# Main.net
KiCad netlist of a schematic drawn in Altium Designer
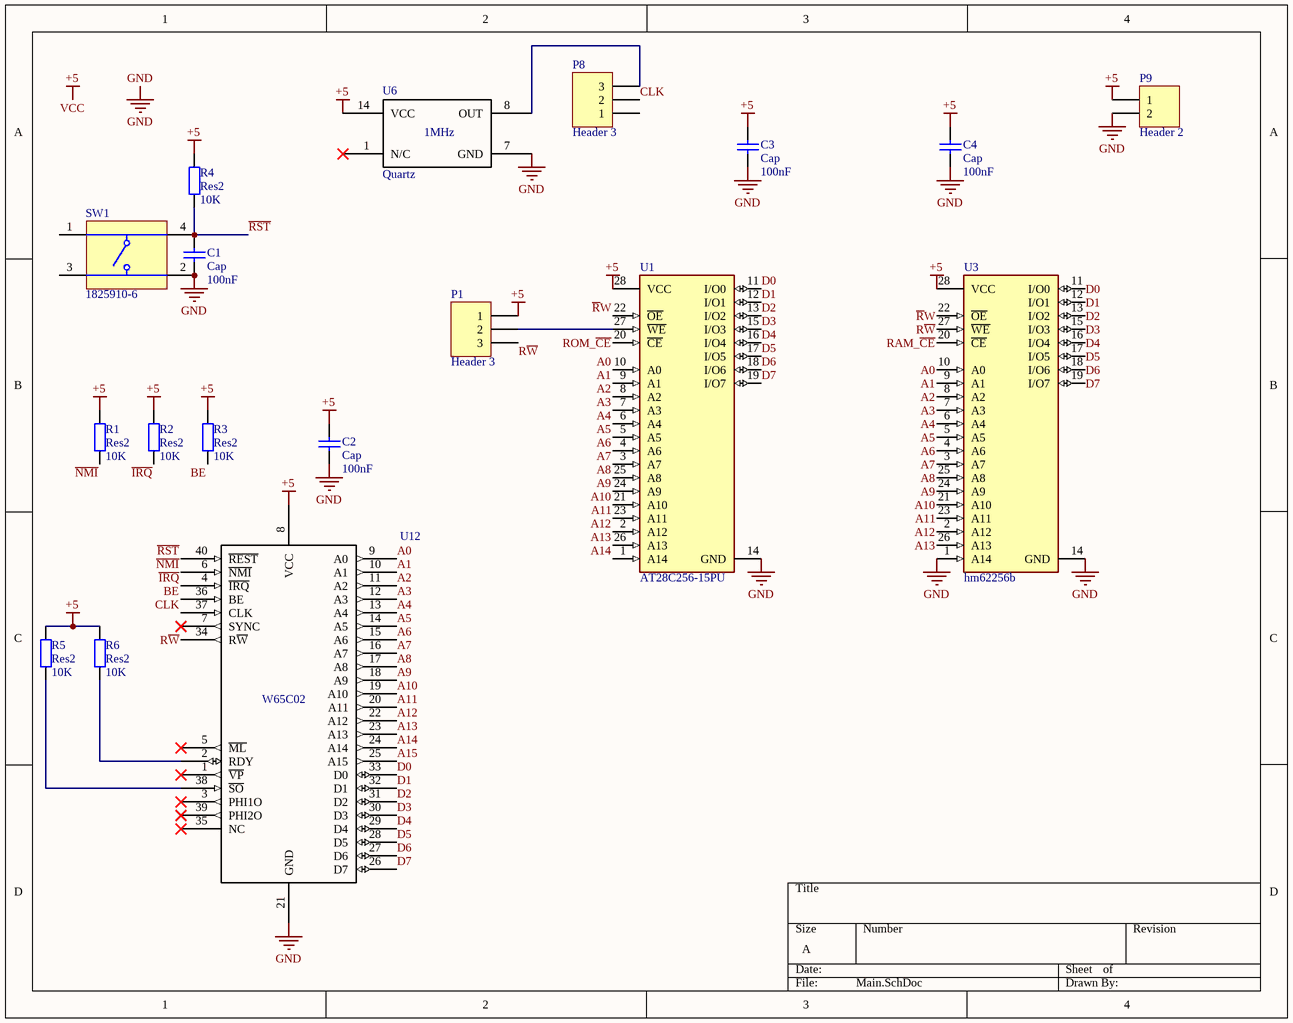
[diagram p0: Main.SchDoc]

(export (version "E")
  (design (tool "Eeschema 10.0.6"))
  (components
    (comp (ref "C1")
      (value "Cap")
      (footprint "Ceramic Capacitor")
      (description "Capacitor")
      (fields (field (name "ALTIUM_VALUE") "100nF") (field (name "PUBLISHER") "Altium Limited"))
      (libsource (lib "Miscellaneous Devices") (part "Cap"))
    )
    (comp (ref "C2")
      (value "Cap")
      (footprint "Ceramic Capacitor")
      (description "Capacitor")
      (fields (field (name "ALTIUM_VALUE") "100nF") (field (name "PUBLISHER") "Altium Limited"))
      (libsource (lib "Miscellaneous Devices") (part "Cap"))
    )
    (comp (ref "C3")
      (value "Cap")
      (footprint "Ceramic Capacitor")
      (description "Capacitor")
      (fields (field (name "ALTIUM_VALUE") "100nF") (field (name "PUBLISHER") "Altium Limited"))
      (libsource (lib "Miscellaneous Devices") (part "Cap"))
    )
    (comp (ref "C4")
      (value "Cap")
      (footprint "Ceramic Capacitor")
      (description "Capacitor")
      (fields (field (name "ALTIUM_VALUE") "100nF") (field (name "PUBLISHER") "Altium Limited"))
      (libsource (lib "Miscellaneous Devices") (part "Cap"))
    )
    (comp (ref "P1")
      (value "Header 3")
      (footprint "HDR1X3")
      (description "Header, 3-Pin")
      (fields (field (name "PUBLISHER") "Altium Limited"))
      (libsource (lib "") (part "Header 3_1"))
    )
    (comp (ref "P8")
      (value "Header 3")
      (footprint "HDR1X3")
      (description "Header, 3-Pin")
      (fields (field (name "PUBLISHER") "Altium Limited"))
      (libsource (lib "Miscellaneous Connectors") (part "Header 3"))
    )
    (comp (ref "P9")
      (value "Header 2")
      (footprint "HDR1X2")
      (description "Header, 2-Pin")
      (fields (field (name "PUBLISHER") "Altium Limited"))
      (libsource (lib "Miscellaneous Connectors") (part "Header 2"))
    )
    (comp (ref "R1")
      (value "Res2")
      (footprint "AXIAL-0.4")
      (description "Resistor")
      (fields (field (name "ALTIUM_VALUE") "10K") (field (name "PUBLISHER") "Altium Limited"))
      (libsource (lib "Miscellaneous Devices") (part "Res2"))
    )
    (comp (ref "R2")
      (value "Res2")
      (footprint "AXIAL-0.4")
      (description "Resistor")
      (fields (field (name "ALTIUM_VALUE") "10K") (field (name "PUBLISHER") "Altium Limited"))
      (libsource (lib "Miscellaneous Devices") (part "Res2"))
    )
    (comp (ref "R3")
      (value "Res2")
      (footprint "AXIAL-0.4")
      (description "Resistor")
      (fields (field (name "ALTIUM_VALUE") "10K") (field (name "PUBLISHER") "Altium Limited"))
      (libsource (lib "Miscellaneous Devices") (part "Res2"))
    )
    (comp (ref "R4")
      (value "Res2")
      (footprint "AXIAL-0.4")
      (description "Resistor")
      (fields (field (name "ALTIUM_VALUE") "10K") (field (name "PUBLISHER") "Altium Limited"))
      (libsource (lib "Miscellaneous Devices") (part "Res2"))
    )
    (comp (ref "R5")
      (value "Res2")
      (footprint "AXIAL-0.4")
      (description "Resistor")
      (fields (field (name "ALTIUM_VALUE") "10K") (field (name "PUBLISHER") "Altium Limited"))
      (libsource (lib "Miscellaneous Devices") (part "Res2"))
    )
    (comp (ref "R6")
      (value "Res2")
      (footprint "AXIAL-0.4")
      (description "Resistor")
      (fields (field (name "ALTIUM_VALUE") "10K") (field (name "PUBLISHER") "Altium Limited"))
      (libsource (lib "Miscellaneous Devices") (part "Res2"))
    )
    (comp (ref "SW1")
      (value "1825910-6")
      (footprint "TECO-1825910-6_V")
      (description "Tact Switch, SPST-NO, 0.05 A, -35 to 85 degC, 4-Pin THD, RoHS, Bulk")
      (fields (field (name "MANUFACTURER") "TE Connectivity"))
      (libsource (lib "Altium Content Vault") (part "SW-SPST-4_A"))
    )
    (comp (ref "U1")
      (value "AT28C256-15PU")
      (footprint "FP-28P6-MFG")
      (description "IC EEPROM 256K PARALLEL 28DIP")
      (fields
        (field (name "MANUFACTURER") "Microchip")
        (field (name "OCTOPART") "https://octopart.com/at28c256-15pu-microchip-77758240")
      )
      (libsource (lib "Altium Content Vault") (part "df06beef5d7b4d1cd730806cb3934f7"))
    )
    (comp (ref "U3")
      (value "hm62256b")
      (footprint "FP-28P6-MFG")
      (description "RAM")
      (fields
        (field (name "MANUFACTURER PART NUMBER") "AT28C256-15PU")
        (field (name "MANUFACTURER") "Microchip")
      )
      (libsource (lib "Altium Content Vault") (part "df06beef5d7b4d1cd730806cb3934f7"))
    )
    (comp (ref "U6") (value "Quartz") (footprint "Quartz") (libsource (lib "Misc") (part "Quartz")))
    (comp (ref "U12") (value "W65C02") (footprint "DIP40") (libsource (lib "Misc") (part "W65C02")))
  )
  (nets
    (net (code "1") (name "+5") (class "Default")
      (node (ref "C2") (pin "1") (pinfunction "1_1") (pintype "passive"))
      (node (ref "C3") (pin "1") (pinfunction "1_1") (pintype "passive"))
      (node (ref "C4") (pin "1") (pinfunction "1_1") (pintype "passive"))
      (node (ref "P1") (pin "1") (pinfunction "1_1") (pintype "passive"))
      (node (ref "P9") (pin "1") (pinfunction "1_1") (pintype "passive"))
      (node (ref "R1") (pin "2") (pinfunction "2_2") (pintype "passive"))
      (node (ref "R2") (pin "2") (pinfunction "2_2") (pintype "passive"))
      (node (ref "R3") (pin "2") (pinfunction "2_2") (pintype "passive"))
      (node (ref "R4") (pin "2") (pinfunction "2_2") (pintype "passive"))
      (node (ref "R5") (pin "2") (pinfunction "2_2") (pintype "passive"))
      (node (ref "R6") (pin "2") (pinfunction "2_2") (pintype "passive"))
      (node (ref "U1") (pin "28") (pinfunction "VCC_28") (pintype "power_in"))
      (node (ref "U12") (pin "8") (pinfunction "VCC_8") (pintype "power_in"))
      (node (ref "U3") (pin "28") (pinfunction "VCC_28") (pintype "power_in"))
      (node (ref "U6") (pin "14") (pinfunction "VCC_14") (pintype "passive"))
    )
    (net (code "2") (name "/A0") (class "Default")
      (node (ref "U1") (pin "10") (pinfunction "A0_10") (pintype "input"))
      (node (ref "U12") (pin "9") (pinfunction "A0_9") (pintype "output"))
      (node (ref "U3") (pin "10") (pinfunction "A0_10") (pintype "input"))
    )
    (net (code "3") (name "/A1") (class "Default")
      (node (ref "U1") (pin "9") (pinfunction "A1_9") (pintype "input"))
      (node (ref "U12") (pin "10") (pinfunction "A1_10") (pintype "output"))
      (node (ref "U3") (pin "9") (pinfunction "A1_9") (pintype "input"))
    )
    (net (code "4") (name "/A2") (class "Default")
      (node (ref "U1") (pin "8") (pinfunction "A2_8") (pintype "input"))
      (node (ref "U12") (pin "11") (pinfunction "A2_11") (pintype "output"))
      (node (ref "U3") (pin "8") (pinfunction "A2_8") (pintype "input"))
    )
    (net (code "5") (name "/A3") (class "Default")
      (node (ref "U1") (pin "7") (pinfunction "A3_7") (pintype "input"))
      (node (ref "U12") (pin "12") (pinfunction "A3_12") (pintype "output"))
      (node (ref "U3") (pin "7") (pinfunction "A3_7") (pintype "input"))
    )
    (net (code "6") (name "/A4") (class "Default")
      (node (ref "U1") (pin "6") (pinfunction "A4_6") (pintype "input"))
      (node (ref "U12") (pin "13") (pinfunction "A4_13") (pintype "output"))
      (node (ref "U3") (pin "6") (pinfunction "A4_6") (pintype "input"))
    )
    (net (code "7") (name "/A5") (class "Default")
      (node (ref "U1") (pin "5") (pinfunction "A5_5") (pintype "input"))
      (node (ref "U12") (pin "14") (pinfunction "A5_14") (pintype "output"))
      (node (ref "U3") (pin "5") (pinfunction "A5_5") (pintype "input"))
    )
    (net (code "8") (name "/A6") (class "Default")
      (node (ref "U1") (pin "4") (pinfunction "A6_4") (pintype "input"))
      (node (ref "U12") (pin "15") (pinfunction "A6_15") (pintype "output"))
      (node (ref "U3") (pin "4") (pinfunction "A6_4") (pintype "input"))
    )
    (net (code "9") (name "/A7") (class "Default")
      (node (ref "U1") (pin "3") (pinfunction "A7_3") (pintype "input"))
      (node (ref "U12") (pin "16") (pinfunction "A7_16") (pintype "output"))
      (node (ref "U3") (pin "3") (pinfunction "A7_3") (pintype "input"))
    )
    (net (code "10") (name "/A8") (class "Default")
      (node (ref "U1") (pin "25") (pinfunction "A8_25") (pintype "input"))
      (node (ref "U12") (pin "17") (pinfunction "A8_17") (pintype "output"))
      (node (ref "U3") (pin "25") (pinfunction "A8_25") (pintype "input"))
    )
    (net (code "11") (name "/A9") (class "Default")
      (node (ref "U1") (pin "24") (pinfunction "A9_24") (pintype "input"))
      (node (ref "U12") (pin "18") (pinfunction "A9_18") (pintype "output"))
      (node (ref "U3") (pin "24") (pinfunction "A9_24") (pintype "input"))
    )
    (net (code "12") (name "/A10") (class "Default")
      (node (ref "U1") (pin "21") (pinfunction "A10_21") (pintype "input"))
      (node (ref "U12") (pin "19") (pinfunction "A10_19") (pintype "output"))
      (node (ref "U3") (pin "21") (pinfunction "A10_21") (pintype "input"))
    )
    (net (code "13") (name "/A11") (class "Default")
      (node (ref "U1") (pin "23") (pinfunction "A11_23") (pintype "input"))
      (node (ref "U12") (pin "20") (pinfunction "A11_20") (pintype "output"))
      (node (ref "U3") (pin "23") (pinfunction "A11_23") (pintype "input"))
    )
    (net (code "14") (name "/A12") (class "Default")
      (node (ref "U1") (pin "2") (pinfunction "A12_2") (pintype "input"))
      (node (ref "U12") (pin "22") (pinfunction "A12_22") (pintype "output"))
      (node (ref "U3") (pin "2") (pinfunction "A12_2") (pintype "input"))
    )
    (net (code "15") (name "/A13") (class "Default")
      (node (ref "U1") (pin "26") (pinfunction "A13_26") (pintype "input"))
      (node (ref "U12") (pin "23") (pinfunction "A13_23") (pintype "output"))
      (node (ref "U3") (pin "26") (pinfunction "A13_26") (pintype "input"))
    )
    (net (code "16") (name "/A14") (class "Default")
      (node (ref "U1") (pin "1") (pinfunction "A14_1") (pintype "input"))
      (node (ref "U12") (pin "24") (pinfunction "A14_24") (pintype "output"))
    )
    (net (code "17") (name "/A15") (class "Default")
      (node (ref "U12") (pin "25") (pinfunction "A15_25") (pintype "output"))
    )
    (net (code "18") (name "/BE") (class "Default")
      (node (ref "R3") (pin "1") (pinfunction "1_1") (pintype "passive"))
      (node (ref "U12") (pin "36") (pinfunction "BE_36") (pintype "input"))
    )
    (net (code "19") (name "/CLK") (class "Default")
      (node (ref "P8") (pin "2") (pinfunction "2_2") (pintype "passive"))
      (node (ref "U12") (pin "37") (pinfunction "CLK_37") (pintype "input"))
    )
    (net (code "20") (name "/D0") (class "Default")
      (node (ref "U1") (pin "11") (pinfunction "I/O0_11") (pintype "bidirectional"))
      (node (ref "U12") (pin "33") (pinfunction "D0_33") (pintype "bidirectional"))
      (node (ref "U3") (pin "11") (pinfunction "I/O0_11") (pintype "bidirectional"))
    )
    (net (code "21") (name "/D1") (class "Default")
      (node (ref "U1") (pin "12") (pinfunction "I/O1_12") (pintype "bidirectional"))
      (node (ref "U12") (pin "32") (pinfunction "D1_32") (pintype "bidirectional"))
      (node (ref "U3") (pin "12") (pinfunction "I/O1_12") (pintype "bidirectional"))
    )
    (net (code "22") (name "/D2") (class "Default")
      (node (ref "U1") (pin "13") (pinfunction "I/O2_13") (pintype "bidirectional"))
      (node (ref "U12") (pin "31") (pinfunction "D2_31") (pintype "bidirectional"))
      (node (ref "U3") (pin "13") (pinfunction "I/O2_13") (pintype "bidirectional"))
    )
    (net (code "23") (name "/D3") (class "Default")
      (node (ref "U1") (pin "15") (pinfunction "I/O3_15") (pintype "bidirectional"))
      (node (ref "U12") (pin "30") (pinfunction "D3_30") (pintype "bidirectional"))
      (node (ref "U3") (pin "15") (pinfunction "I/O3_15") (pintype "bidirectional"))
    )
    (net (code "24") (name "/D4") (class "Default")
      (node (ref "U1") (pin "16") (pinfunction "I/O4_16") (pintype "bidirectional"))
      (node (ref "U12") (pin "29") (pinfunction "D4_29") (pintype "bidirectional"))
      (node (ref "U3") (pin "16") (pinfunction "I/O4_16") (pintype "bidirectional"))
    )
    (net (code "25") (name "/D5") (class "Default")
      (node (ref "U1") (pin "17") (pinfunction "I/O5_17") (pintype "bidirectional"))
      (node (ref "U12") (pin "28") (pinfunction "D5_28") (pintype "bidirectional"))
      (node (ref "U3") (pin "17") (pinfunction "I/O5_17") (pintype "bidirectional"))
    )
    (net (code "26") (name "/D6") (class "Default")
      (node (ref "U1") (pin "18") (pinfunction "I/O6_18") (pintype "bidirectional"))
      (node (ref "U12") (pin "27") (pinfunction "D6_27") (pintype "bidirectional"))
      (node (ref "U3") (pin "18") (pinfunction "I/O6_18") (pintype "bidirectional"))
    )
    (net (code "27") (name "/D7") (class "Default")
      (node (ref "U1") (pin "19") (pinfunction "I/O7_19") (pintype "bidirectional"))
      (node (ref "U12") (pin "26") (pinfunction "D7_26") (pintype "bidirectional"))
      (node (ref "U3") (pin "19") (pinfunction "I/O7_19") (pintype "bidirectional"))
    )
    (net (code "28") (name "/RAM_~{CE}") (class "Default")
      (node (ref "U3") (pin "20") (pinfunction "~{CE}_20") (pintype "input"))
    )
    (net (code "29") (name "/ROM_~{CE}") (class "Default")
      (node (ref "U1") (pin "20") (pinfunction "~{CE}_20") (pintype "input"))
    )
    (net (code "30") (name "/R~{W}") (class "Default")
      (node (ref "P1") (pin "3") (pinfunction "3_3") (pintype "passive"))
      (node (ref "U12") (pin "34") (pinfunction "R~{W}_34") (pintype "output"))
      (node (ref "U3") (pin "27") (pinfunction "~{WE}_27") (pintype "input"))
    )
    (net (code "31") (name "/~{IRQ}") (class "Default")
      (node (ref "R2") (pin "1") (pinfunction "1_1") (pintype "passive"))
      (node (ref "U12") (pin "4") (pinfunction "~{IRQ}_4") (pintype "input"))
    )
    (net (code "32") (name "/~{NMI}") (class "Default")
      (node (ref "R1") (pin "1") (pinfunction "1_1") (pintype "passive"))
      (node (ref "U12") (pin "6") (pinfunction "~{NMI}_6") (pintype "input"))
    )
    (net (code "33") (name "/~{RST}") (class "Default")
      (node (ref "C1") (pin "1") (pinfunction "1_1") (pintype "passive"))
      (node (ref "R4") (pin "1") (pinfunction "1_1") (pintype "passive"))
      (node (ref "SW1") (pin "4") (pinfunction "4_4") (pintype "passive"))
      (node (ref "U12") (pin "40") (pinfunction "~{REST}_40") (pintype "input"))
    )
    (net (code "34") (name "/~{R}W") (class "Default")
      (node (ref "U1") (pin "22") (pinfunction "~{OE}_22") (pintype "input"))
      (node (ref "U3") (pin "22") (pinfunction "~{OE}_22") (pintype "input"))
    )
    (net (code "35") (name "GND") (class "Default")
      (node (ref "C1") (pin "2") (pinfunction "2_2") (pintype "passive"))
      (node (ref "C2") (pin "2") (pinfunction "2_2") (pintype "passive"))
      (node (ref "C3") (pin "2") (pinfunction "2_2") (pintype "passive"))
      (node (ref "C4") (pin "2") (pinfunction "2_2") (pintype "passive"))
      (node (ref "P9") (pin "2") (pinfunction "2_2") (pintype "passive"))
      (node (ref "SW1") (pin "2") (pinfunction "2_2") (pintype "passive"))
      (node (ref "U1") (pin "14") (pinfunction "GND_14") (pintype "power_in"))
      (node (ref "U12") (pin "21") (pinfunction "GND_21") (pintype "power_in"))
      (node (ref "U3") (pin "1") (pinfunction "A14_1") (pintype "input"))
      (node (ref "U3") (pin "14") (pinfunction "GND_14") (pintype "power_in"))
      (node (ref "U6") (pin "7") (pinfunction "GND_7") (pintype "passive"))
    )
    (net (code "36") (name "Net-(U1-~{WE})") (class "Default")
      (node (ref "P1") (pin "2") (pinfunction "2_2") (pintype "passive"))
      (node (ref "U1") (pin "27") (pinfunction "~{WE}_27") (pintype "input"))
    )
    (net (code "37") (name "Net-(U6-OUT)") (class "Default")
      (node (ref "P8") (pin "3") (pinfunction "3_3") (pintype "passive"))
      (node (ref "U6") (pin "8") (pinfunction "OUT_8") (pintype "passive"))
    )
    (net (code "38") (name "Net-(U12-RDY)") (class "Default")
      (node (ref "R6") (pin "1") (pinfunction "1_1") (pintype "passive"))
      (node (ref "U12") (pin "2") (pinfunction "RDY_2") (pintype "bidirectional"))
    )
    (net (code "39") (name "Net-(U12-~{SO})") (class "Default")
      (node (ref "R5") (pin "1") (pinfunction "1_1") (pintype "passive"))
      (node (ref "U12") (pin "38") (pinfunction "~{SO}_38") (pintype "input"))
    )
    (net (code "40") (name "unconnected-(P8-Pad1)") (class "Default")
      (node (ref "P8") (pin "1") (pinfunction "1_1") (pintype "passive"))
    )
    (net (code "41") (name "unconnected-(SW1-Pad1)") (class "Default")
      (node (ref "SW1") (pin "1") (pinfunction "1_1") (pintype "passive"))
    )
    (net (code "42") (name "unconnected-(SW1-Pad3)") (class "Default")
      (node (ref "SW1") (pin "3") (pinfunction "3_3") (pintype "passive"))
    )
    (net (code "43") (name "unconnected-(U6-N{slash}C-Pad1)") (class "Default")
      (node (ref "U6") (pin "1") (pinfunction "N/C_1") (pintype "passive+no_connect"))
    )
    (net (code "44") (name "unconnected-(U12-NC-Pad35)") (class "Default")
      (node (ref "U12") (pin "35") (pinfunction "NC_35") (pintype "passive+no_connect"))
    )
    (net (code "45") (name "unconnected-(U12-PHI1O-Pad3)") (class "Default")
      (node (ref "U12") (pin "3") (pinfunction "PHI1O_3") (pintype "output+no_connect"))
    )
    (net (code "46") (name "unconnected-(U12-PHI2O-Pad39)") (class "Default")
      (node (ref "U12") (pin "39") (pinfunction "PHI2O_39") (pintype "output+no_connect"))
    )
    (net (code "47") (name "unconnected-(U12-SYNC-Pad7)") (class "Default")
      (node (ref "U12") (pin "7") (pinfunction "SYNC_7") (pintype "output+no_connect"))
    )
    (net (code "48") (name "unconnected-(U12-~{ML}-Pad5)") (class "Default")
      (node (ref "U12") (pin "5") (pinfunction "~{ML}_5") (pintype "output+no_connect"))
    )
    (net (code "49") (name "unconnected-(U12-~{VP}-Pad1)") (class "Default")
      (node (ref "U12") (pin "1") (pinfunction "~{VP}_1") (pintype "output+no_connect"))
    )
  )
)
